# Power.net
KiCad netlist of a schematic drawn in Altium Designer
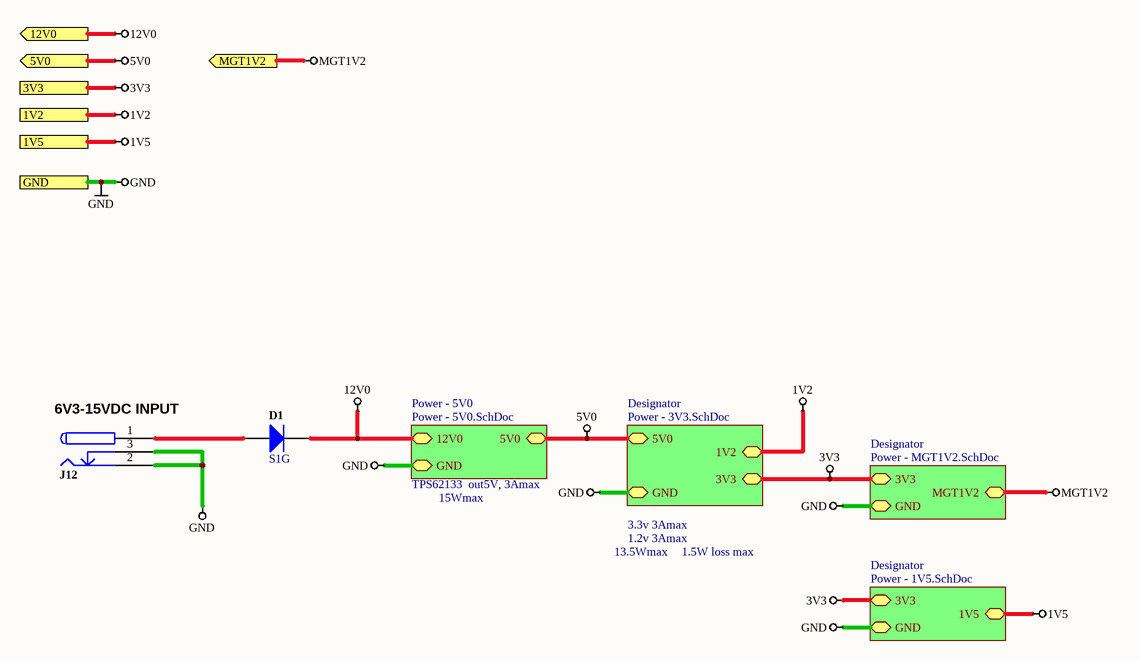
[diagram p0: Power.SchDoc]

(export (version "E")
  (design (tool "Eeschema 10.0.6"))
  (components
    (comp (ref "D1")
      (value "S1G")
      (footprint "DO-214AC")
      (description "Fairchild S1G General Purpose Rectifier")
      (libsource (lib "DIODE-S1G") (part "S1G"))
    )
    (comp (ref "J12")
      (value "PWR CONNECTOR")
      (footprint "PJ-102AH")
      (description "Connector, 3 Conductor Power Jack")
      (fields (field (name "MANUFACTURER PART NUMBER") "CP-102AH-ND"))
      (libsource (lib "PWR_CONNECTOR_3") (part "POWER-CONNECTOR-3"))
    )
  )
  (nets
    (net (code "5") (name "12V0") (class "Default")
      (node (ref "D1") (pin "2") (pinfunction "2_2") (pintype "passive"))
    )
    (net (code "6") (name "GND") (class "Default")
      (node (ref "J12") (pin "2") (pintype "power_in"))
      (node (ref "J12") (pin "3") (pintype "power_in"))
    )
    (net (code "8") (name "Net-(D1-Pad1)") (class "Default")
      (node (ref "D1") (pin "1") (pinfunction "1_1") (pintype "passive"))
      (node (ref "J12") (pin "1") (pintype "power_in"))
    )
  )
)
